# 3_3V_StepDown.net
KiCad netlist of a schematic drawn in EAGLE
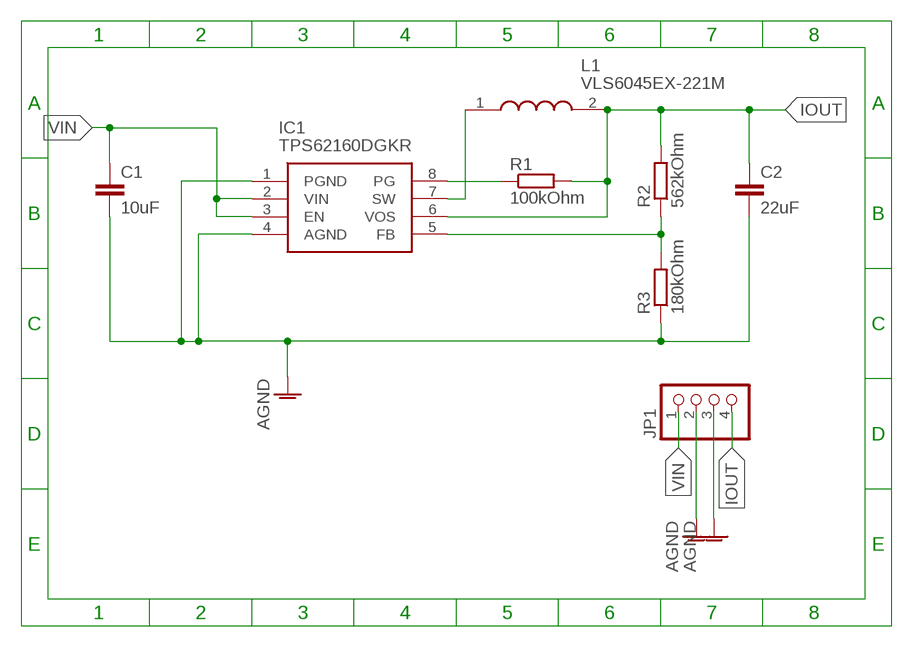
[diagram p0: schematic, sheet 1]

(export (version "E")
  (design (tool "Eeschema 10.0.6"))
  (components
    (comp (ref "C1")
      (value "10uF")
      (footprint "eagle-import:C1206")
      (libsource (lib "eagle-import") (part "CNC5L1X7R1C106K160AEC1206"))
    )
    (comp (ref "C2")
      (value "22uF")
      (footprint "eagle-import:C0805K")
      (libsource (lib "eagle-import") (part "GRM219R61C226ME15KC0805K"))
    )
    (comp (ref "IC1")
      (value "TPS62160DGKR")
      (footprint "eagle-import:SOP65P490X110-8N")
      (fields (field (name "MOUSER_PART_NUMBER") "595-TPS62160DGKR"))
      (libsource (lib "eagle-import") (part "TPS62160DGKR"))
    )
    (comp (ref "JP1")
      (value "PINHD-1X4")
      (footprint "eagle-import:1X04")
      (libsource (lib "eagle-import") (part "PINHD-1X4"))
    )
    (comp (ref "L1")
      (value "VLS6045EX-221M")
      (footprint "eagle-import:INDPM6060X450N")
      (fields
        (field (name "MOUSER_PART_NUMBER") "810-VLS6045EX-221M")
        (field (name "RS_PART_NUMBER") "1247062")
      )
      (libsource (lib "eagle-import") (part "VLS6045EX-221M"))
    )
    (comp (ref "R1")
      (value "100kOhm")
      (footprint "eagle-import:R1206")
      (libsource (lib "eagle-import") (part "RCS1206100KJNEAR1206"))
    )
    (comp (ref "R2")
      (value "562kOhm")
      (footprint "eagle-import:R0805")
      (libsource (lib "eagle-import") (part "ERJ-PB6B5623VR0805"))
    )
    (comp (ref "R3")
      (value "180kOhm")
      (footprint "eagle-import:R0402")
      (libsource (lib "eagle-import") (part "RN73R1ETTP1803D25R0402"))
    )
  )
  (nets
    (net (code "1") (name "AGND") (class "Default")
      (node (ref "C1") (pin "2") (pinfunction "2_2") (pintype "passive"))
      (node (ref "C2") (pin "2") (pinfunction "2_2") (pintype "passive"))
      (node (ref "IC1") (pin "1") (pinfunction "PGND_1") (pintype "bidirectional"))
      (node (ref "IC1") (pin "4") (pinfunction "AGND_4") (pintype "bidirectional"))
      (node (ref "JP1") (pin "2") (pinfunction "2_2") (pintype "passive"))
      (node (ref "JP1") (pin "3") (pinfunction "3_3") (pintype "passive"))
      (node (ref "R3") (pin "1") (pinfunction "1_1") (pintype "passive"))
    )
    (net (code "2") (name "IOUT") (class "Default")
      (node (ref "C2") (pin "1") (pinfunction "1_1") (pintype "passive"))
      (node (ref "IC1") (pin "6") (pinfunction "VOS_6") (pintype "bidirectional"))
      (node (ref "JP1") (pin "4") (pinfunction "4_4") (pintype "passive"))
      (node (ref "L1") (pin "2") (pinfunction "2_2") (pintype "bidirectional"))
      (node (ref "R1") (pin "2") (pinfunction "2_2") (pintype "passive"))
      (node (ref "R2") (pin "2") (pinfunction "2_2") (pintype "passive"))
    )
    (net (code "3") (name "Net-(IC1-FB)") (class "Default")
      (node (ref "IC1") (pin "5") (pinfunction "FB_5") (pintype "bidirectional"))
      (node (ref "R2") (pin "1") (pinfunction "1_1") (pintype "passive"))
      (node (ref "R3") (pin "2") (pinfunction "2_2") (pintype "passive"))
    )
    (net (code "4") (name "Net-(IC1-PG)") (class "Default")
      (node (ref "IC1") (pin "8") (pinfunction "PG_8") (pintype "bidirectional"))
      (node (ref "R1") (pin "1") (pinfunction "1_1") (pintype "passive"))
    )
    (net (code "5") (name "Net-(IC1-SW)") (class "Default")
      (node (ref "IC1") (pin "7") (pinfunction "SW_7") (pintype "bidirectional"))
      (node (ref "L1") (pin "1") (pinfunction "1_1") (pintype "bidirectional"))
    )
    (net (code "6") (name "VIN") (class "Default")
      (node (ref "C1") (pin "1") (pinfunction "1_1") (pintype "passive"))
      (node (ref "IC1") (pin "2") (pinfunction "VIN_2") (pintype "bidirectional"))
      (node (ref "IC1") (pin "3") (pinfunction "EN_3") (pintype "bidirectional"))
      (node (ref "JP1") (pin "1") (pinfunction "1_1") (pintype "passive"))
    )
  )
)
